# 2_-_Battery_Sensing_and_Control.net
KiCad netlist of a schematic drawn in Altium Designer
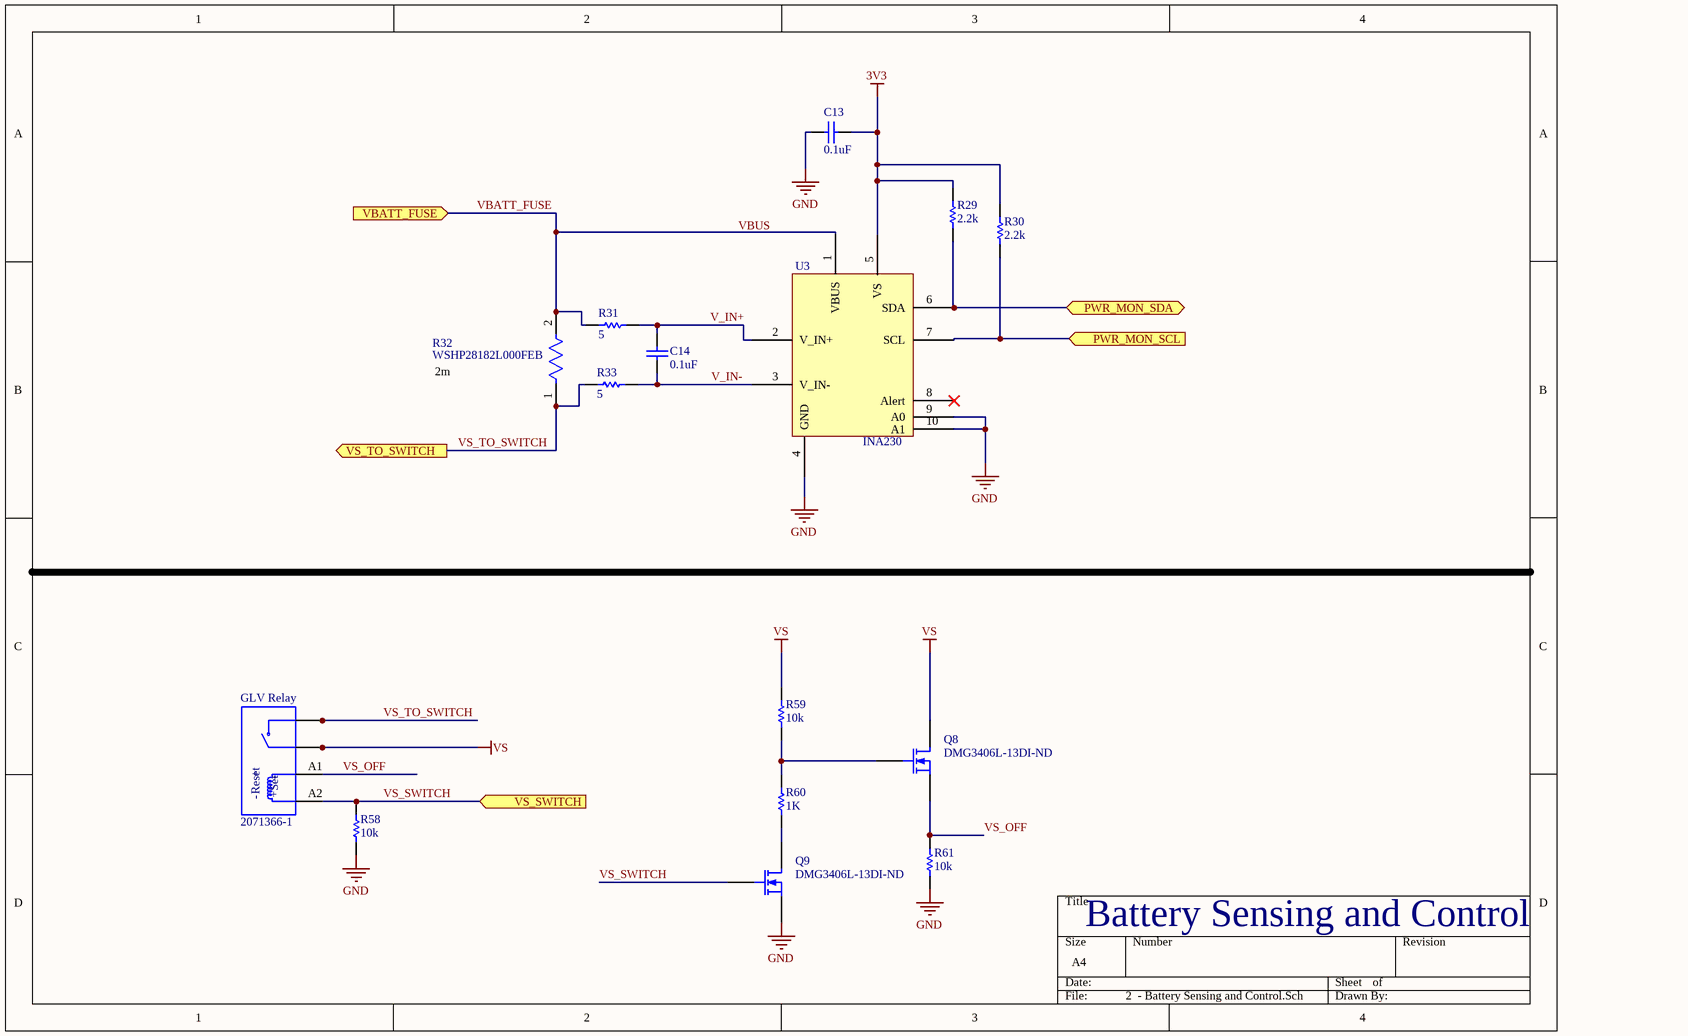
[diagram p0: 2  - Battery Sensing and Control.SchDoc]

(export (version "E")
  (design (tool "Eeschema 10.0.6"))
  (components
    (comp (ref "C13")
      (value "0.1uF")
      (footprint "0603R-generic")
      (description "Capacitor")
      (fields
        (field (name "MANUFACTURER") "Yageo")
        (field (name "MANUFACTURER PART NUMBER") "CC1210ZKY5V8BB106")
      )
      (libsource (lib "Miscellaneous Devices") (part "Cap"))
    )
    (comp (ref "C14")
      (value "0.1uF")
      (footprint "0603R-generic")
      (description "Capacitor")
      (fields
        (field (name "MANUFACTURER") "Yageo")
        (field (name "MANUFACTURER PART NUMBER") "CC1210ZKY5V8BB106")
      )
      (libsource (lib "Miscellaneous Devices") (part "Cap"))
    )
    (comp (ref "GLV Relay")
      (value "2071366-1")
      (footprint "TE_2071366-1")
      (description "Power Relay, 12Vdc, 60A, Spst-No, Tht")
      (fields (field (name "MF") "TE Connectivity") (field (name "DIGI-KEY_PART_NUMBER") "PB2134-ND"))
      (libsource (lib "SnapEDAsch") (part "2071366-1"))
    )
    (comp (ref "Q8")
      (value "~")
      (footprint "SOT-23_N")
      (description "N-Channel MOSFET")
      (fields
        (field (name "MANUFACTURER") "Infineon Technologies")
        (field (name "MANUFACTURER PART NUMBER") "IPD075N03L G")
        (field (name "SUPPLIER PART NUMBER 1") "DMG3406L-13DI-ND")
        (field (name "PUBLISHER") "Altium Limited")
      )
      (libsource (lib "Miscellaneous Devices") (part "MOSFET-N"))
    )
    (comp (ref "Q9")
      (value "~")
      (footprint "SOT-23_N")
      (description "N-Channel MOSFET")
      (fields
        (field (name "MANUFACTURER") "Infineon Technologies")
        (field (name "MANUFACTURER PART NUMBER") "IPD075N03L G")
        (field (name "SUPPLIER PART NUMBER 1") "DMG3406L-13DI-ND")
        (field (name "PUBLISHER") "Altium Limited")
      )
      (libsource (lib "Miscellaneous Devices") (part "MOSFET-N"))
    )
    (comp (ref "R29")
      (value "2.2k")
      (footprint "RESC0603(1608)_L")
      (description "0603 (1608 Metric) Chip Resistor")
      (libsource (lib "Altium Content Vault") (part "RES_3"))
    )
    (comp (ref "R30")
      (value "2.2k")
      (footprint "RESC0603(1608)_L")
      (description "0603 (1608 Metric) Chip Resistor")
      (libsource (lib "Altium Content Vault") (part "RES_3"))
    )
    (comp (ref "R31")
      (value "5")
      (footprint "RESC0603(1608)_L")
      (description "0603 (1608 Metric) Chip Resistor")
      (libsource (lib "Altium Content Vault") (part "RES_3"))
    )
    (comp (ref "R32")
      (value "WSHP28182L000FEB")
      (footprint "FP-WSHP2818-MFG")
      (description "WSHP28182L000FEB Res Metal Strip 2818 0.002 Ohm 1% 10W ±200ppm/C Pad SMD Automotive T/R")
      (fields (field (name "TOLERANCE") "1%"))
      (libsource (lib "Altium Content Vault") (part "1029c3af85768c4190bb7ad29bc67b5"))
    )
    (comp (ref "R33")
      (value "5")
      (footprint "RESC0603(1608)_L")
      (description "0603 (1608 Metric) Chip Resistor")
      (libsource (lib "Altium Content Vault") (part "RES_3"))
    )
    (comp (ref "R58")
      (value "10k")
      (footprint "RESC0603(1608)_L")
      (description "0603 (1608 Metric) Chip Resistor")
      (libsource (lib "Altium Content Vault") (part "RES_3"))
    )
    (comp (ref "R59")
      (value "10k")
      (footprint "RESC0603(1608)_L")
      (description "0603 (1608 Metric) Chip Resistor")
      (libsource (lib "Altium Content Vault") (part "RES_3"))
    )
    (comp (ref "R60")
      (value "1K")
      (footprint "RESC0603(1608)_L")
      (description "0603 (1608 Metric) Chip Resistor")
      (libsource (lib "Altium Content Vault") (part "RES_3"))
    )
    (comp (ref "R61")
      (value "10k")
      (footprint "RESC0603(1608)_L")
      (description "0603 (1608 Metric) Chip Resistor")
      (libsource (lib "Altium Content Vault") (part "RES_3"))
    )
    (comp (ref "U3")
      (value "INA230")
      (footprint "SOP50P490X110-10N")
      (libsource (lib "ACB_lib") (part "INA230"))
    )
  )
  (nets
    (net (code "1") (name "/PWR_MON_SCL") (class "Default")
      (node (ref "R30") (pin "1") (pinfunction "1_1") (pintype "passive"))
      (node (ref "U3") (pin "7") (pinfunction "SCL_7") (pintype "passive"))
    )
    (net (code "2") (name "/PWR_MON_SDA") (class "Default")
      (node (ref "R29") (pin "1") (pinfunction "1_1") (pintype "passive"))
      (node (ref "U3") (pin "6") (pinfunction "SDA_6") (pintype "passive"))
    )
    (net (code "3") (name "/VBATT_FUSE") (class "Default")
      (node (ref "R31") (pin "2") (pinfunction "2_2") (pintype "passive"))
      (node (ref "R32") (pin "2") (pinfunction "2_2") (pintype "passive"))
      (node (ref "U3") (pin "1") (pinfunction "VBUS_1") (pintype "passive"))
    )
    (net (code "5") (name "/VS_OFF") (class "Default")
      (node (ref "GLV Relay") (pin "A1") (pinfunction "A1_A1") (pintype "passive"))
      (node (ref "Q8") (pin "2") (pinfunction "S_2") (pintype "passive"))
      (node (ref "R61") (pin "1") (pinfunction "1_1") (pintype "passive"))
    )
    (net (code "6") (name "/VS_SWITCH") (class "Default")
      (node (ref "GLV Relay") (pin "A2") (pinfunction "A2_A2") (pintype "passive"))
      (node (ref "Q9") (pin "1") (pinfunction "G_1") (pintype "passive"))
      (node (ref "R58") (pin "2") (pinfunction "2_2") (pintype "passive"))
    )
    (net (code "7") (name "/VS_TO_SWITCH") (class "Default")
      (node (ref "GLV Relay") (pin "1") (pinfunction "1_1") (pintype "passive"))
      (node (ref "GLV Relay") (pin "2") (pinfunction "1_2") (pintype "passive"))
      (node (ref "GLV Relay") (pin "3") (pinfunction "1_3") (pintype "passive"))
      (node (ref "R32") (pin "1") (pinfunction "1_1") (pintype "passive"))
      (node (ref "R33") (pin "2") (pinfunction "2_2") (pintype "passive"))
    )
    (net (code "8") (name "/V_IN+") (class "Default")
      (node (ref "C14") (pin "2") (pinfunction "2_2") (pintype "passive"))
      (node (ref "R31") (pin "1") (pinfunction "1_1") (pintype "passive"))
      (node (ref "U3") (pin "2") (pinfunction "V_IN+_2") (pintype "passive"))
    )
    (net (code "9") (name "/V_IN-") (class "Default")
      (node (ref "C14") (pin "1") (pinfunction "1_1") (pintype "passive"))
      (node (ref "R33") (pin "1") (pinfunction "1_1") (pintype "passive"))
      (node (ref "U3") (pin "3") (pinfunction "V_IN-_3") (pintype "passive"))
    )
    (net (code "10") (name "3V3") (class "Default")
      (node (ref "C13") (pin "1") (pinfunction "1_1") (pintype "passive"))
      (node (ref "R29") (pin "2") (pinfunction "2_2") (pintype "passive"))
      (node (ref "R30") (pin "2") (pinfunction "2_2") (pintype "passive"))
      (node (ref "U3") (pin "5") (pinfunction "VS_5") (pintype "passive"))
    )
    (net (code "11") (name "GND") (class "Default")
      (node (ref "C13") (pin "2") (pinfunction "2_2") (pintype "passive"))
      (node (ref "Q9") (pin "2") (pinfunction "S_2") (pintype "passive"))
      (node (ref "R58") (pin "1") (pinfunction "1_1") (pintype "passive"))
      (node (ref "R61") (pin "2") (pinfunction "2_2") (pintype "passive"))
      (node (ref "U3") (pin "10") (pinfunction "A1_10") (pintype "passive"))
      (node (ref "U3") (pin "4") (pinfunction "GND_4") (pintype "passive"))
      (node (ref "U3") (pin "9") (pinfunction "A0_9") (pintype "passive"))
    )
    (net (code "12") (name "Net-(Q8-G)") (class "Default")
      (node (ref "Q8") (pin "1") (pinfunction "G_1") (pintype "passive"))
      (node (ref "R59") (pin "2") (pinfunction "2_2") (pintype "passive"))
      (node (ref "R60") (pin "2") (pinfunction "2_2") (pintype "passive"))
    )
    (net (code "13") (name "Net-(Q9-D)") (class "Default")
      (node (ref "Q9") (pin "3") (pinfunction "D_3") (pintype "passive"))
      (node (ref "R60") (pin "1") (pinfunction "1_1") (pintype "passive"))
    )
    (net (code "14") (name "VS") (class "Default")
      (node (ref "GLV Relay") (pin "4") (pinfunction "2_4") (pintype "passive"))
      (node (ref "GLV Relay") (pin "5") (pinfunction "2_5") (pintype "passive"))
      (node (ref "GLV Relay") (pin "6") (pinfunction "2_6") (pintype "passive"))
      (node (ref "Q8") (pin "3") (pinfunction "D_3") (pintype "passive"))
      (node (ref "R59") (pin "1") (pinfunction "1_1") (pintype "passive"))
    )
    (net (code "15") (name "unconnected-(U3-Alert-Pad8)") (class "Default")
      (node (ref "U3") (pin "8") (pinfunction "Alert_8") (pintype "passive+no_connect"))
    )
  )
)
